# 14_LCD_TS_CT.net
KiCad netlist of a schematic drawn in Altium Designer
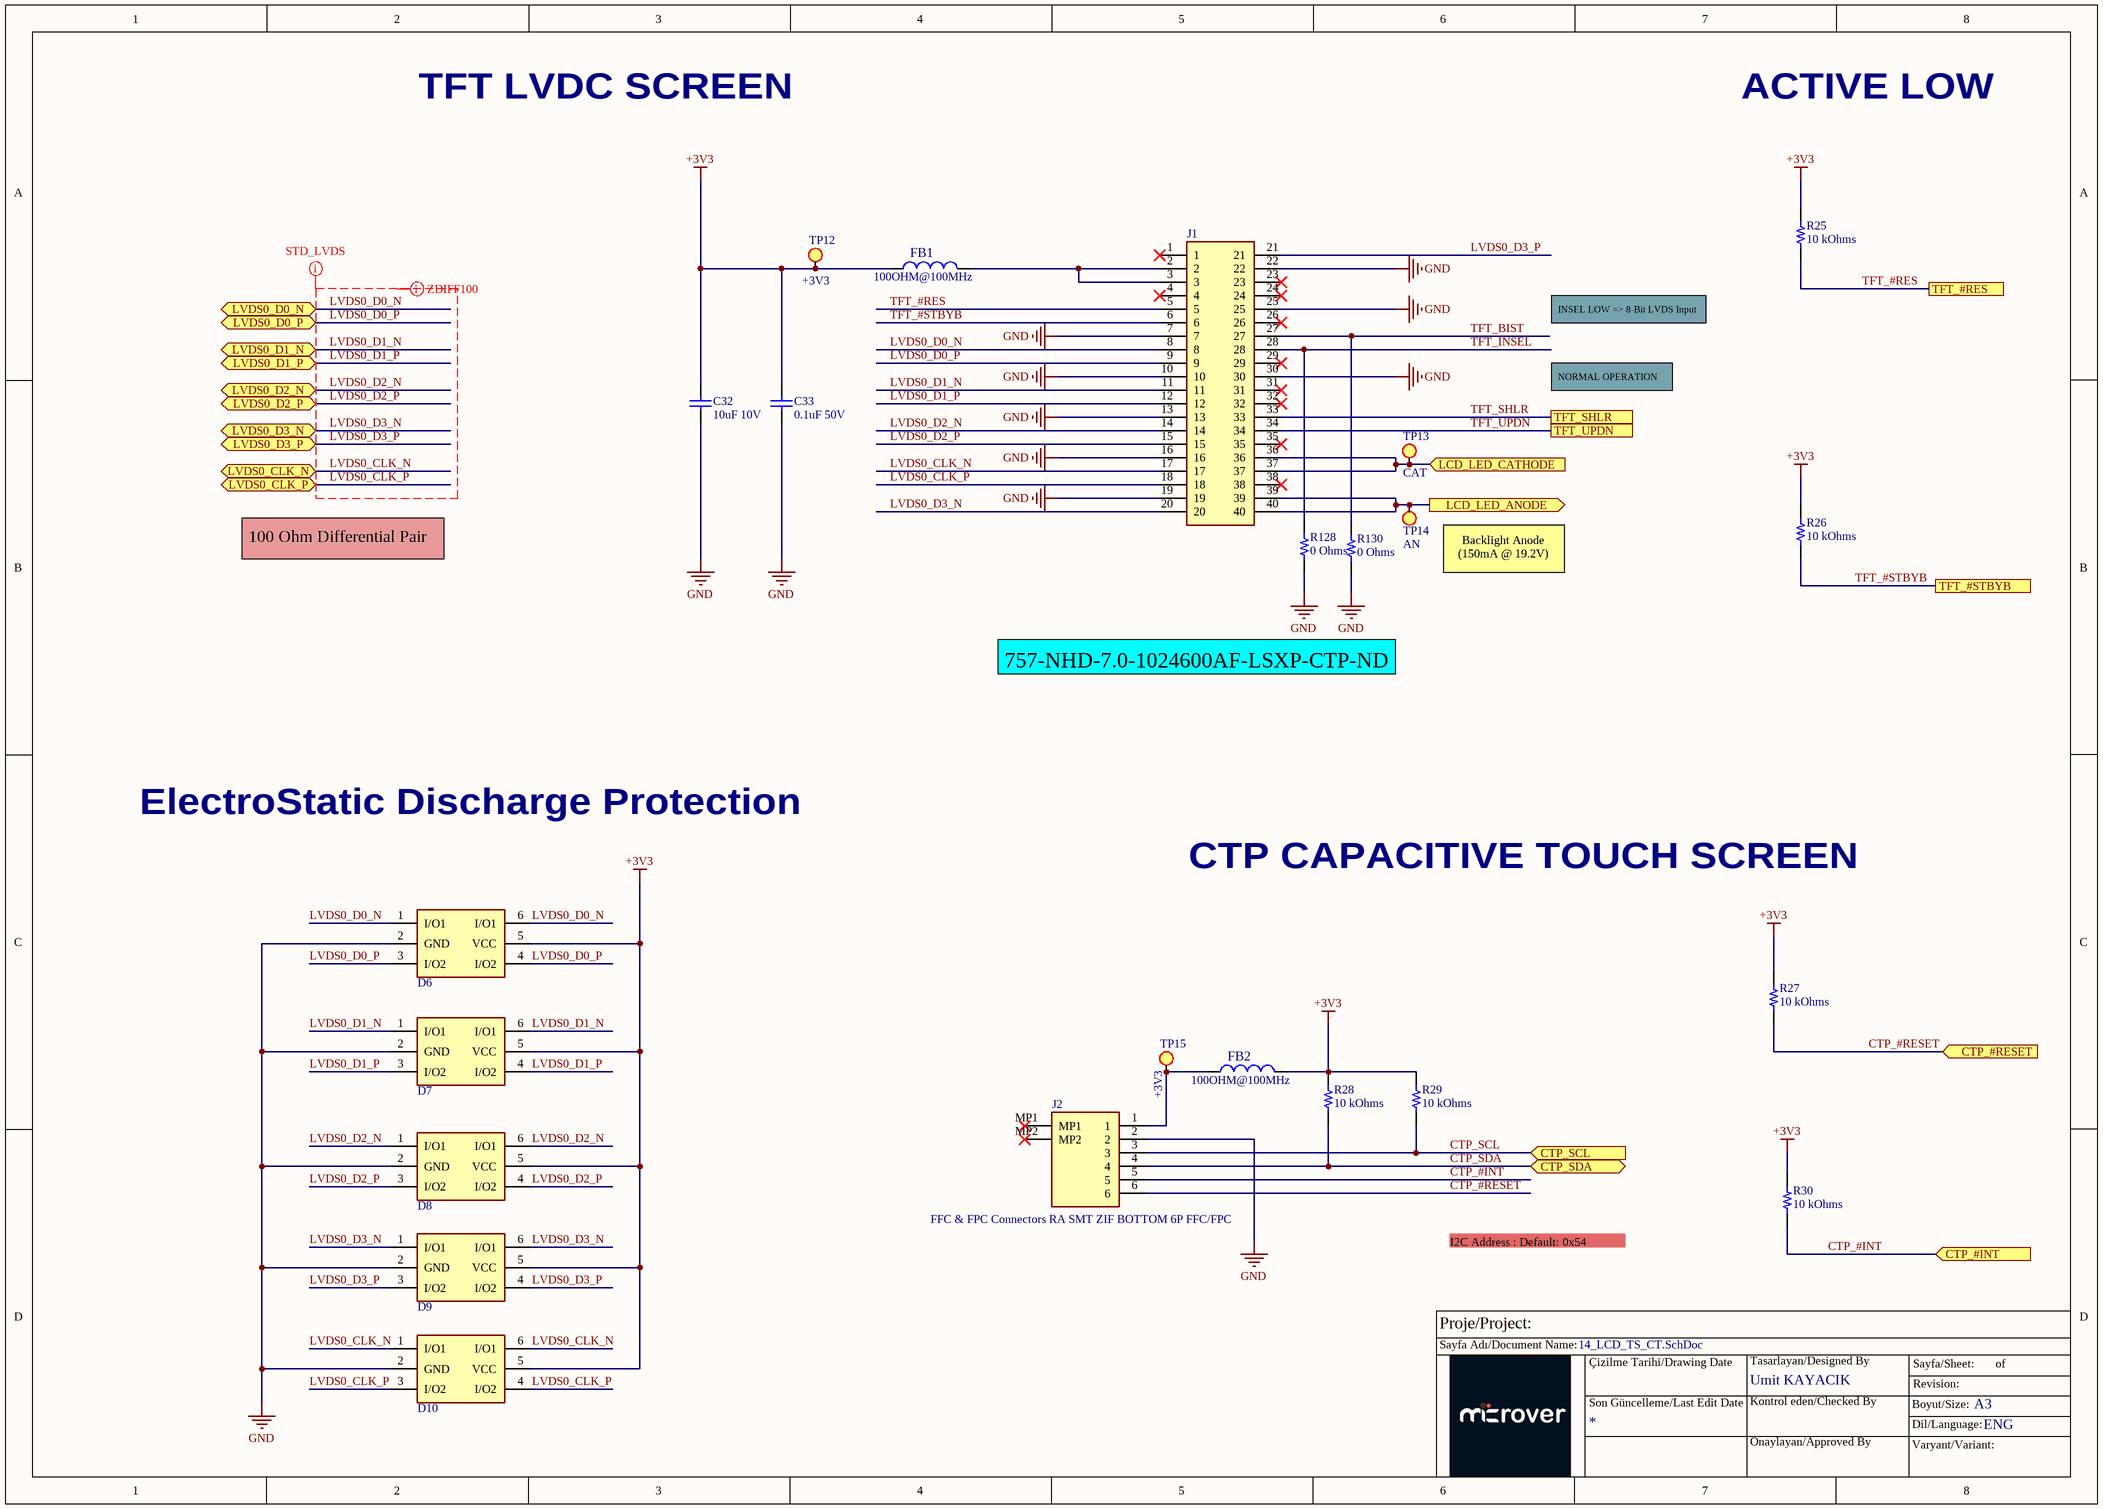
[diagram p0: 14_LCD_TS_CT.SchDoc]

(export (version "E")
  (design (tool "Eeschema 10.0.6"))
  (components
    (comp (ref "C32")
      (value "10uF 10V")
      (footprint "SMC1206")
      (description "10 µF ±10% 10V Ceramic Capacitor X7R 1206 (3216 Metric)")
      (fields
        (field (name "MANUFACTURER PART NUMBER") "CL31B106KPHNNNE")
        (field (name "LCSC PART NUMBER") "C96449")
      )
      (libsource (lib "HW_HOLLAND_NCDM_MONITOR_R1") (part "CAP1206_10UF_10V"))
    )
    (comp (ref "C33")
      (value "0.1uF 50V")
      (footprint "SMC0603")
      (description "0.1 µF ±10% 50V Ceramic Capacitor X7R 0603 (1608 Metric)")
      (fields
        (field (name "MANUFACTURER PART NUMBER") "CL10B104KB8NNNL")
        (field (name "LCSC PART NUMBER") "C1591")
      )
      (libsource (lib "HW_HOLLAND_NCDM_MONITOR_R1") (part "CAP0603_0.1UF_50V"))
    )
    (comp (ref "D6")
      (value "SON-6(1x1.5) ESD Protection Devices ROHS")
      (footprint "Nexperia_SOT886_MFG")
      (fields
        (field (name "MANUFACTURER PART NUMBER") "PRTR5V0U2F")
        (field (name "LCSC PART NUMBER") "C2937001")
      )
      (libsource (lib "HW_HOLLAND_NCDM_MONITOR_R1") (part "PRTR5V0U2F"))
    )
    (comp (ref "D7")
      (value "SON-6(1x1.5) ESD Protection Devices ROHS")
      (footprint "Nexperia_SOT886_MFG")
      (fields
        (field (name "MANUFACTURER PART NUMBER") "PRTR5V0U2F")
        (field (name "LCSC PART NUMBER") "C2937001")
      )
      (libsource (lib "HW_HOLLAND_NCDM_MONITOR_R1") (part "PRTR5V0U2F"))
    )
    (comp (ref "D8")
      (value "SON-6(1x1.5) ESD Protection Devices ROHS")
      (footprint "Nexperia_SOT886_MFG")
      (fields
        (field (name "MANUFACTURER PART NUMBER") "PRTR5V0U2F")
        (field (name "LCSC PART NUMBER") "C2937001")
      )
      (libsource (lib "HW_HOLLAND_NCDM_MONITOR_R1") (part "PRTR5V0U2F"))
    )
    (comp (ref "D9")
      (value "SON-6(1x1.5) ESD Protection Devices ROHS")
      (footprint "Nexperia_SOT886_MFG")
      (fields
        (field (name "MANUFACTURER PART NUMBER") "PRTR5V0U2F")
        (field (name "LCSC PART NUMBER") "C2937001")
      )
      (libsource (lib "HW_HOLLAND_NCDM_MONITOR_R1") (part "PRTR5V0U2F"))
    )
    (comp (ref "D10")
      (value "SON-6(1x1.5) ESD Protection Devices ROHS")
      (footprint "Nexperia_SOT886_MFG")
      (fields
        (field (name "MANUFACTURER PART NUMBER") "PRTR5V0U2F")
        (field (name "LCSC PART NUMBER") "C2937001")
      )
      (libsource (lib "HW_HOLLAND_NCDM_MONITOR_R1") (part "PRTR5V0U2F"))
    )
    (comp (ref "FB1")
      (value "100OHM@100MHz")
      (footprint "FB 0603(1608)")
      (description "100 Ohms @ 100 MHz 1 Power Line Ferrite Bead 0603 (1608 Metric) 2A 40mOhm")
      (fields
        (field (name "MANUFACTURER") "TDK")
        (field (name "MANUFACTURER PART NUMBER") "MPZ1608Y101BTA00")
      )
      (libsource (lib "HW_HOLLAND_NCDM_MONITOR_R1") (part "FB0603_100OHM_100MHz"))
    )
    (comp (ref "FB2")
      (value "100OHM@100MHz")
      (footprint "FB 0603(1608)")
      (description "100 Ohms @ 100 MHz 1 Power Line Ferrite Bead 0603 (1608 Metric) 2A 40mOhm")
      (fields
        (field (name "MANUFACTURER") "TDK")
        (field (name "MANUFACTURER PART NUMBER") "MPZ1608Y101BTA00")
      )
      (libsource (lib "HW_HOLLAND_NCDM_MONITOR_R1") (part "FB0603_100OHM_100MHz"))
    )
    (comp (ref "J1")
      (value "FFC & FPC Connectors 0.5 FPC ZIF SMT R/AU prCont40CktEmbsTpPk")
      (footprint "54104-4031")
      (description "Conn FFC/FPC Connector SKT 40 POS 0.5mm Solder RA SMD Easy-On™ T/R")
      (fields (field (name "MANUFACTURER") "Molex") (field (name "MANUFACTURER PART NUMBER") "54104-4031"))
      (libsource (lib "HW_HOLLAND_NCDM_MONITOR_R1") (part "54104-4031"))
    )
    (comp (ref "J2")
      (value "FFC & FPC Connectors RA SMT ZIF BOTTOM 6P FFC/FPC")
      (footprint "522710679")
      (description "FFC/FPC SMT SER 1mm Pitch 6Way RightAngle SMT Female FPC Conn; ZIF Bottom Contact")
      (fields (field (name "MANUFACTURER") "Molex") (field (name "MANUFACTURER PART NUMBER") "52271-0679"))
      (libsource (lib "HW_HOLLAND_NCDM_MONITOR_R1") (part "52271-0679"))
    )
    (comp (ref "R25")
      (value "10 kOhms")
      (footprint "RES 0402_1005")
      (description "RES 10K OHM 0.1% 1/10W 0402")
      (fields
        (field (name "PART NUMBER") "RP73PF1E10KBTD")
        (field (name "MANUFACTURER") "TE Connectivity Passive Product")
      )
      (libsource (lib "Celestial Altium Library - altium_library") (part "Resistor"))
    )
    (comp (ref "R26")
      (value "10 kOhms")
      (footprint "RES 0402_1005")
      (description "RES 10K OHM 0.1% 1/10W 0402")
      (fields
        (field (name "PART NUMBER") "RP73PF1E10KBTD")
        (field (name "MANUFACTURER") "TE Connectivity Passive Product")
      )
      (libsource (lib "Celestial Altium Library - altium_library") (part "Resistor"))
    )
    (comp (ref "R27")
      (value "10 kOhms")
      (footprint "RES 0402_1005")
      (description "RES 10K OHM 0.1% 1/10W 0402")
      (fields
        (field (name "PART NUMBER") "RP73PF1E10KBTD")
        (field (name "MANUFACTURER") "TE Connectivity Passive Product")
      )
      (libsource (lib "Celestial Altium Library - altium_library") (part "Resistor"))
    )
    (comp (ref "R28")
      (value "10 kOhms")
      (footprint "RES 0402_1005")
      (description "RES 10K OHM 0.1% 1/10W 0402")
      (fields
        (field (name "PART NUMBER") "RP73PF1E10KBTD")
        (field (name "MANUFACTURER") "TE Connectivity Passive Product")
      )
      (libsource (lib "Celestial Altium Library - altium_library") (part "Resistor"))
    )
    (comp (ref "R29")
      (value "10 kOhms")
      (footprint "RES 0402_1005")
      (description "RES 10K OHM 0.1% 1/10W 0402")
      (fields
        (field (name "PART NUMBER") "RP73PF1E10KBTD")
        (field (name "MANUFACTURER") "TE Connectivity Passive Product")
      )
      (libsource (lib "Celestial Altium Library - altium_library") (part "Resistor"))
    )
    (comp (ref "R30")
      (value "10 kOhms")
      (footprint "RES 0402_1005")
      (description "RES 10K OHM 0.1% 1/10W 0402")
      (fields
        (field (name "PART NUMBER") "RP73PF1E10KBTD")
        (field (name "MANUFACTURER") "TE Connectivity Passive Product")
      )
      (libsource (lib "Celestial Altium Library - altium_library") (part "Resistor"))
    )
    (comp (ref "R128")
      (value "0 Ohms")
      (footprint "RES0402(1005)")
      (description "RES 0 OHM JUMPER 1/8W 0402")
      (fields
        (field (name "PART NUMBER") "HCJ0402ZT0R00")
        (field (name "MANUFACTURER") "Stackpole Electronics Inc")
      )
      (libsource (lib "Celestial Altium Library - altium_library") (part "Resistor"))
    )
    (comp (ref "R130")
      (value "0 Ohms")
      (footprint "RES0402(1005)")
      (description "RES 0 OHM JUMPER 1/8W 0402")
      (fields
        (field (name "PART NUMBER") "HCJ0402ZT0R00")
        (field (name "MANUFACTURER") "Stackpole Electronics Inc")
      )
      (libsource (lib "Celestial Altium Library - altium_library") (part "Resistor"))
    )
    (comp (ref "TP12")
      (value "+3V3")
      (footprint "TEST_POINT")
      (libsource (lib "HW_HOLLAND_NCDM_MONITOR_R1") (part "TP_1"))
    )
    (comp (ref "TP13")
      (value "CAT")
      (footprint "TEST_POINT")
      (libsource (lib "HW_HOLLAND_NCDM_MONITOR_R1") (part "TP_1"))
    )
    (comp (ref "TP14")
      (value "AN")
      (footprint "TEST_POINT")
      (libsource (lib "HW_HOLLAND_NCDM_MONITOR_R1") (part "TP_1"))
    )
    (comp (ref "TP15")
      (value "+3V3")
      (footprint "TEST_POINT")
      (libsource (lib "HW_HOLLAND_NCDM_MONITOR_R1") (part "TP_1"))
    )
  )
  (nets
    (net (code "1") (name "+3V3") (class "Default")
      (node (ref "C32") (pin "2") (pinfunction "2_2") (pintype "passive"))
      (node (ref "C33") (pin "2") (pinfunction "2_2") (pintype "passive"))
      (node (ref "D10") (pin "5") (pinfunction "VCC_5") (pintype "power_in"))
      (node (ref "D6") (pin "5") (pinfunction "VCC_5") (pintype "power_in"))
      (node (ref "D7") (pin "5") (pinfunction "VCC_5") (pintype "power_in"))
      (node (ref "D8") (pin "5") (pinfunction "VCC_5") (pintype "power_in"))
      (node (ref "D9") (pin "5") (pinfunction "VCC_5") (pintype "power_in"))
      (node (ref "FB1") (pin "2") (pinfunction "2_2") (pintype "passive"))
      (node (ref "FB2") (pin "1") (pinfunction "1_1") (pintype "passive"))
      (node (ref "R25") (pin "2") (pinfunction "2_2") (pintype "passive"))
      (node (ref "R26") (pin "2") (pinfunction "2_2") (pintype "passive"))
      (node (ref "R27") (pin "2") (pinfunction "2_2") (pintype "passive"))
      (node (ref "R28") (pin "2") (pinfunction "2_2") (pintype "passive"))
      (node (ref "R29") (pin "2") (pinfunction "2_2") (pintype "passive"))
      (node (ref "R30") (pin "2") (pinfunction "2_2") (pintype "passive"))
      (node (ref "TP12") (pin "1") (pinfunction "TP_1") (pintype "passive"))
    )
    (net (code "2") (name "/CTP_#INT") (class "Default")
      (node (ref "J2") (pin "5") (pinfunction "5_5") (pintype "passive"))
      (node (ref "R30") (pin "1") (pinfunction "1_1") (pintype "passive"))
    )
    (net (code "3") (name "/CTP_#RESET") (class "Default")
      (node (ref "J2") (pin "6") (pinfunction "6_6") (pintype "passive"))
      (node (ref "R27") (pin "1") (pinfunction "1_1") (pintype "passive"))
    )
    (net (code "4") (name "/CTP_SCL") (class "Default")
      (node (ref "J2") (pin "3") (pinfunction "3_3") (pintype "passive"))
      (node (ref "R29") (pin "1") (pinfunction "1_1") (pintype "passive"))
    )
    (net (code "5") (name "/CTP_SDA") (class "Default")
      (node (ref "J2") (pin "4") (pinfunction "4_4") (pintype "passive"))
      (node (ref "R28") (pin "1") (pinfunction "1_1") (pintype "passive"))
    )
    (net (code "6") (name "/LCD_LED_ANODE") (class "Default")
      (node (ref "J1") (pin "39") (pinfunction "39_39") (pintype "passive"))
      (node (ref "J1") (pin "40") (pinfunction "40_40") (pintype "passive"))
      (node (ref "TP14") (pin "1") (pinfunction "TP_1") (pintype "passive"))
    )
    (net (code "7") (name "/LCD_LED_CATHODE") (class "Default")
      (node (ref "J1") (pin "36") (pinfunction "36_36") (pintype "passive"))
      (node (ref "J1") (pin "37") (pinfunction "37_37") (pintype "passive"))
      (node (ref "TP13") (pin "1") (pinfunction "TP_1") (pintype "passive"))
    )
    (net (code "8") (name "/LVDS0_CLK_N") (class "Default")
      (node (ref "D10") (pin "1") (pinfunction "I/O1_1") (pintype "passive"))
      (node (ref "D10") (pin "6") (pinfunction "I/O1_6") (pintype "passive"))
      (node (ref "J1") (pin "17") (pinfunction "17_17") (pintype "passive"))
    )
    (net (code "9") (name "/LVDS0_CLK_P") (class "Default")
      (node (ref "D10") (pin "3") (pinfunction "I/O2_3") (pintype "passive"))
      (node (ref "D10") (pin "4") (pinfunction "I/O2_4") (pintype "passive"))
      (node (ref "J1") (pin "18") (pinfunction "18_18") (pintype "passive"))
    )
    (net (code "10") (name "/LVDS0_D0_N") (class "Default")
      (node (ref "D6") (pin "1") (pinfunction "I/O1_1") (pintype "passive"))
      (node (ref "D6") (pin "6") (pinfunction "I/O1_6") (pintype "passive"))
      (node (ref "J1") (pin "8") (pinfunction "8_8") (pintype "passive"))
    )
    (net (code "11") (name "/LVDS0_D0_P") (class "Default")
      (node (ref "D6") (pin "3") (pinfunction "I/O2_3") (pintype "passive"))
      (node (ref "D6") (pin "4") (pinfunction "I/O2_4") (pintype "passive"))
      (node (ref "J1") (pin "9") (pinfunction "9_9") (pintype "passive"))
    )
    (net (code "12") (name "/LVDS0_D1_N") (class "Default")
      (node (ref "D7") (pin "1") (pinfunction "I/O1_1") (pintype "passive"))
      (node (ref "D7") (pin "6") (pinfunction "I/O1_6") (pintype "passive"))
      (node (ref "J1") (pin "11") (pinfunction "11_11") (pintype "passive"))
    )
    (net (code "13") (name "/LVDS0_D1_P") (class "Default")
      (node (ref "D7") (pin "3") (pinfunction "I/O2_3") (pintype "passive"))
      (node (ref "D7") (pin "4") (pinfunction "I/O2_4") (pintype "passive"))
      (node (ref "J1") (pin "12") (pinfunction "12_12") (pintype "passive"))
    )
    (net (code "14") (name "/LVDS0_D2_N") (class "Default")
      (node (ref "D8") (pin "1") (pinfunction "I/O1_1") (pintype "passive"))
      (node (ref "D8") (pin "6") (pinfunction "I/O1_6") (pintype "passive"))
      (node (ref "J1") (pin "14") (pinfunction "14_14") (pintype "passive"))
    )
    (net (code "15") (name "/LVDS0_D2_P") (class "Default")
      (node (ref "D8") (pin "3") (pinfunction "I/O2_3") (pintype "passive"))
      (node (ref "D8") (pin "4") (pinfunction "I/O2_4") (pintype "passive"))
      (node (ref "J1") (pin "15") (pinfunction "15_15") (pintype "passive"))
    )
    (net (code "16") (name "/LVDS0_D3_N") (class "Default")
      (node (ref "D9") (pin "1") (pinfunction "I/O1_1") (pintype "passive"))
      (node (ref "D9") (pin "6") (pinfunction "I/O1_6") (pintype "passive"))
      (node (ref "J1") (pin "20") (pinfunction "20_20") (pintype "passive"))
    )
    (net (code "17") (name "/LVDS0_D3_P") (class "Default")
      (node (ref "D9") (pin "3") (pinfunction "I/O2_3") (pintype "passive"))
      (node (ref "D9") (pin "4") (pinfunction "I/O2_4") (pintype "passive"))
      (node (ref "J1") (pin "21") (pinfunction "21_21") (pintype "passive"))
    )
    (net (code "18") (name "/TFT_#RES") (class "Default")
      (node (ref "J1") (pin "5") (pinfunction "5_5") (pintype "passive"))
      (node (ref "R25") (pin "1") (pinfunction "1_1") (pintype "passive"))
    )
    (net (code "19") (name "/TFT_#STBYB") (class "Default")
      (node (ref "J1") (pin "6") (pinfunction "6_6") (pintype "passive"))
      (node (ref "R26") (pin "1") (pinfunction "1_1") (pintype "passive"))
    )
    (net (code "20") (name "/TFT_BIST") (class "Default")
      (node (ref "J1") (pin "27") (pinfunction "27_27") (pintype "passive"))
      (node (ref "R130") (pin "1") (pinfunction "1_1") (pintype "passive"))
    )
    (net (code "21") (name "/TFT_INSEL") (class "Default")
      (node (ref "J1") (pin "28") (pinfunction "28_28") (pintype "passive"))
      (node (ref "R128") (pin "1") (pinfunction "1_1") (pintype "passive"))
    )
    (net (code "22") (name "/TFT_SHLR") (class "Default")
      (node (ref "J1") (pin "33") (pinfunction "33_33") (pintype "passive"))
    )
    (net (code "23") (name "/TFT_UPDN") (class "Default")
      (node (ref "J1") (pin "34") (pinfunction "34_34") (pintype "passive"))
    )
    (net (code "24") (name "GND") (class "Default")
      (node (ref "C32") (pin "1") (pinfunction "1_1") (pintype "passive"))
      (node (ref "C33") (pin "1") (pinfunction "1_1") (pintype "passive"))
      (node (ref "D10") (pin "2") (pinfunction "GND_2") (pintype "passive"))
      (node (ref "D6") (pin "2") (pinfunction "GND_2") (pintype "passive"))
      (node (ref "D7") (pin "2") (pinfunction "GND_2") (pintype "passive"))
      (node (ref "D8") (pin "2") (pinfunction "GND_2") (pintype "passive"))
      (node (ref "D9") (pin "2") (pinfunction "GND_2") (pintype "passive"))
      (node (ref "J1") (pin "10") (pinfunction "10_10") (pintype "passive"))
      (node (ref "J1") (pin "13") (pinfunction "13_13") (pintype "passive"))
      (node (ref "J1") (pin "16") (pinfunction "16_16") (pintype "passive"))
      (node (ref "J1") (pin "19") (pinfunction "19_19") (pintype "passive"))
      (node (ref "J1") (pin "22") (pinfunction "22_22") (pintype "passive"))
      (node (ref "J1") (pin "25") (pinfunction "25_25") (pintype "passive"))
      (node (ref "J1") (pin "30") (pinfunction "30_30") (pintype "passive"))
      (node (ref "J1") (pin "7") (pinfunction "7_7") (pintype "passive"))
      (node (ref "J2") (pin "2") (pinfunction "2_2") (pintype "passive"))
      (node (ref "R128") (pin "2") (pinfunction "2_2") (pintype "passive"))
      (node (ref "R130") (pin "2") (pinfunction "2_2") (pintype "passive"))
    )
    (net (code "25") (name "Net-(FB1-Pad1)") (class "Default")
      (node (ref "FB1") (pin "1") (pinfunction "1_1") (pintype "passive"))
      (node (ref "J1") (pin "2") (pinfunction "2_2") (pintype "passive"))
      (node (ref "J1") (pin "3") (pinfunction "3_3") (pintype "passive"))
    )
    (net (code "26") (name "Net-(TP15-TP)") (class "Default")
      (node (ref "FB2") (pin "2") (pinfunction "2_2") (pintype "passive"))
      (node (ref "J2") (pin "1") (pinfunction "1_1") (pintype "passive"))
      (node (ref "TP15") (pin "1") (pinfunction "TP_1") (pintype "passive"))
    )
    (net (code "27") (name "unconnected-(J1-Pad1)") (class "Default")
      (node (ref "J1") (pin "1") (pinfunction "1_1") (pintype "passive+no_connect"))
    )
    (net (code "28") (name "unconnected-(J1-Pad4)") (class "Default")
      (node (ref "J1") (pin "4") (pinfunction "4_4") (pintype "passive+no_connect"))
    )
    (net (code "29") (name "unconnected-(J1-Pad23)") (class "Default")
      (node (ref "J1") (pin "23") (pinfunction "23_23") (pintype "passive+no_connect"))
    )
    (net (code "30") (name "unconnected-(J1-Pad24)") (class "Default")
      (node (ref "J1") (pin "24") (pinfunction "24_24") (pintype "passive+no_connect"))
    )
    (net (code "31") (name "unconnected-(J1-Pad26)") (class "Default")
      (node (ref "J1") (pin "26") (pinfunction "26_26") (pintype "passive+no_connect"))
    )
    (net (code "32") (name "unconnected-(J1-Pad29)") (class "Default")
      (node (ref "J1") (pin "29") (pinfunction "29_29") (pintype "passive+no_connect"))
    )
    (net (code "33") (name "unconnected-(J1-Pad31)") (class "Default")
      (node (ref "J1") (pin "31") (pinfunction "31_31") (pintype "passive+no_connect"))
    )
    (net (code "34") (name "unconnected-(J1-Pad32)") (class "Default")
      (node (ref "J1") (pin "32") (pinfunction "32_32") (pintype "passive+no_connect"))
    )
    (net (code "35") (name "unconnected-(J1-Pad35)") (class "Default")
      (node (ref "J1") (pin "35") (pinfunction "35_35") (pintype "passive+no_connect"))
    )
    (net (code "36") (name "unconnected-(J1-Pad38)") (class "Default")
      (node (ref "J1") (pin "38") (pinfunction "38_38") (pintype "passive+no_connect"))
    )
    (net (code "37") (name "unconnected-(J2-PadMP1)") (class "Default")
      (node (ref "J2") (pin "MP1") (pinfunction "MP1_MP1") (pintype "passive+no_connect"))
    )
    (net (code "38") (name "unconnected-(J2-PadMP2)") (class "Default")
      (node (ref "J2") (pin "MP2") (pinfunction "MP2_MP2") (pintype "passive+no_connect"))
    )
  )
)
